# Stepper_Motor6.net
KiCad netlist of a schematic drawn in Altium Designer
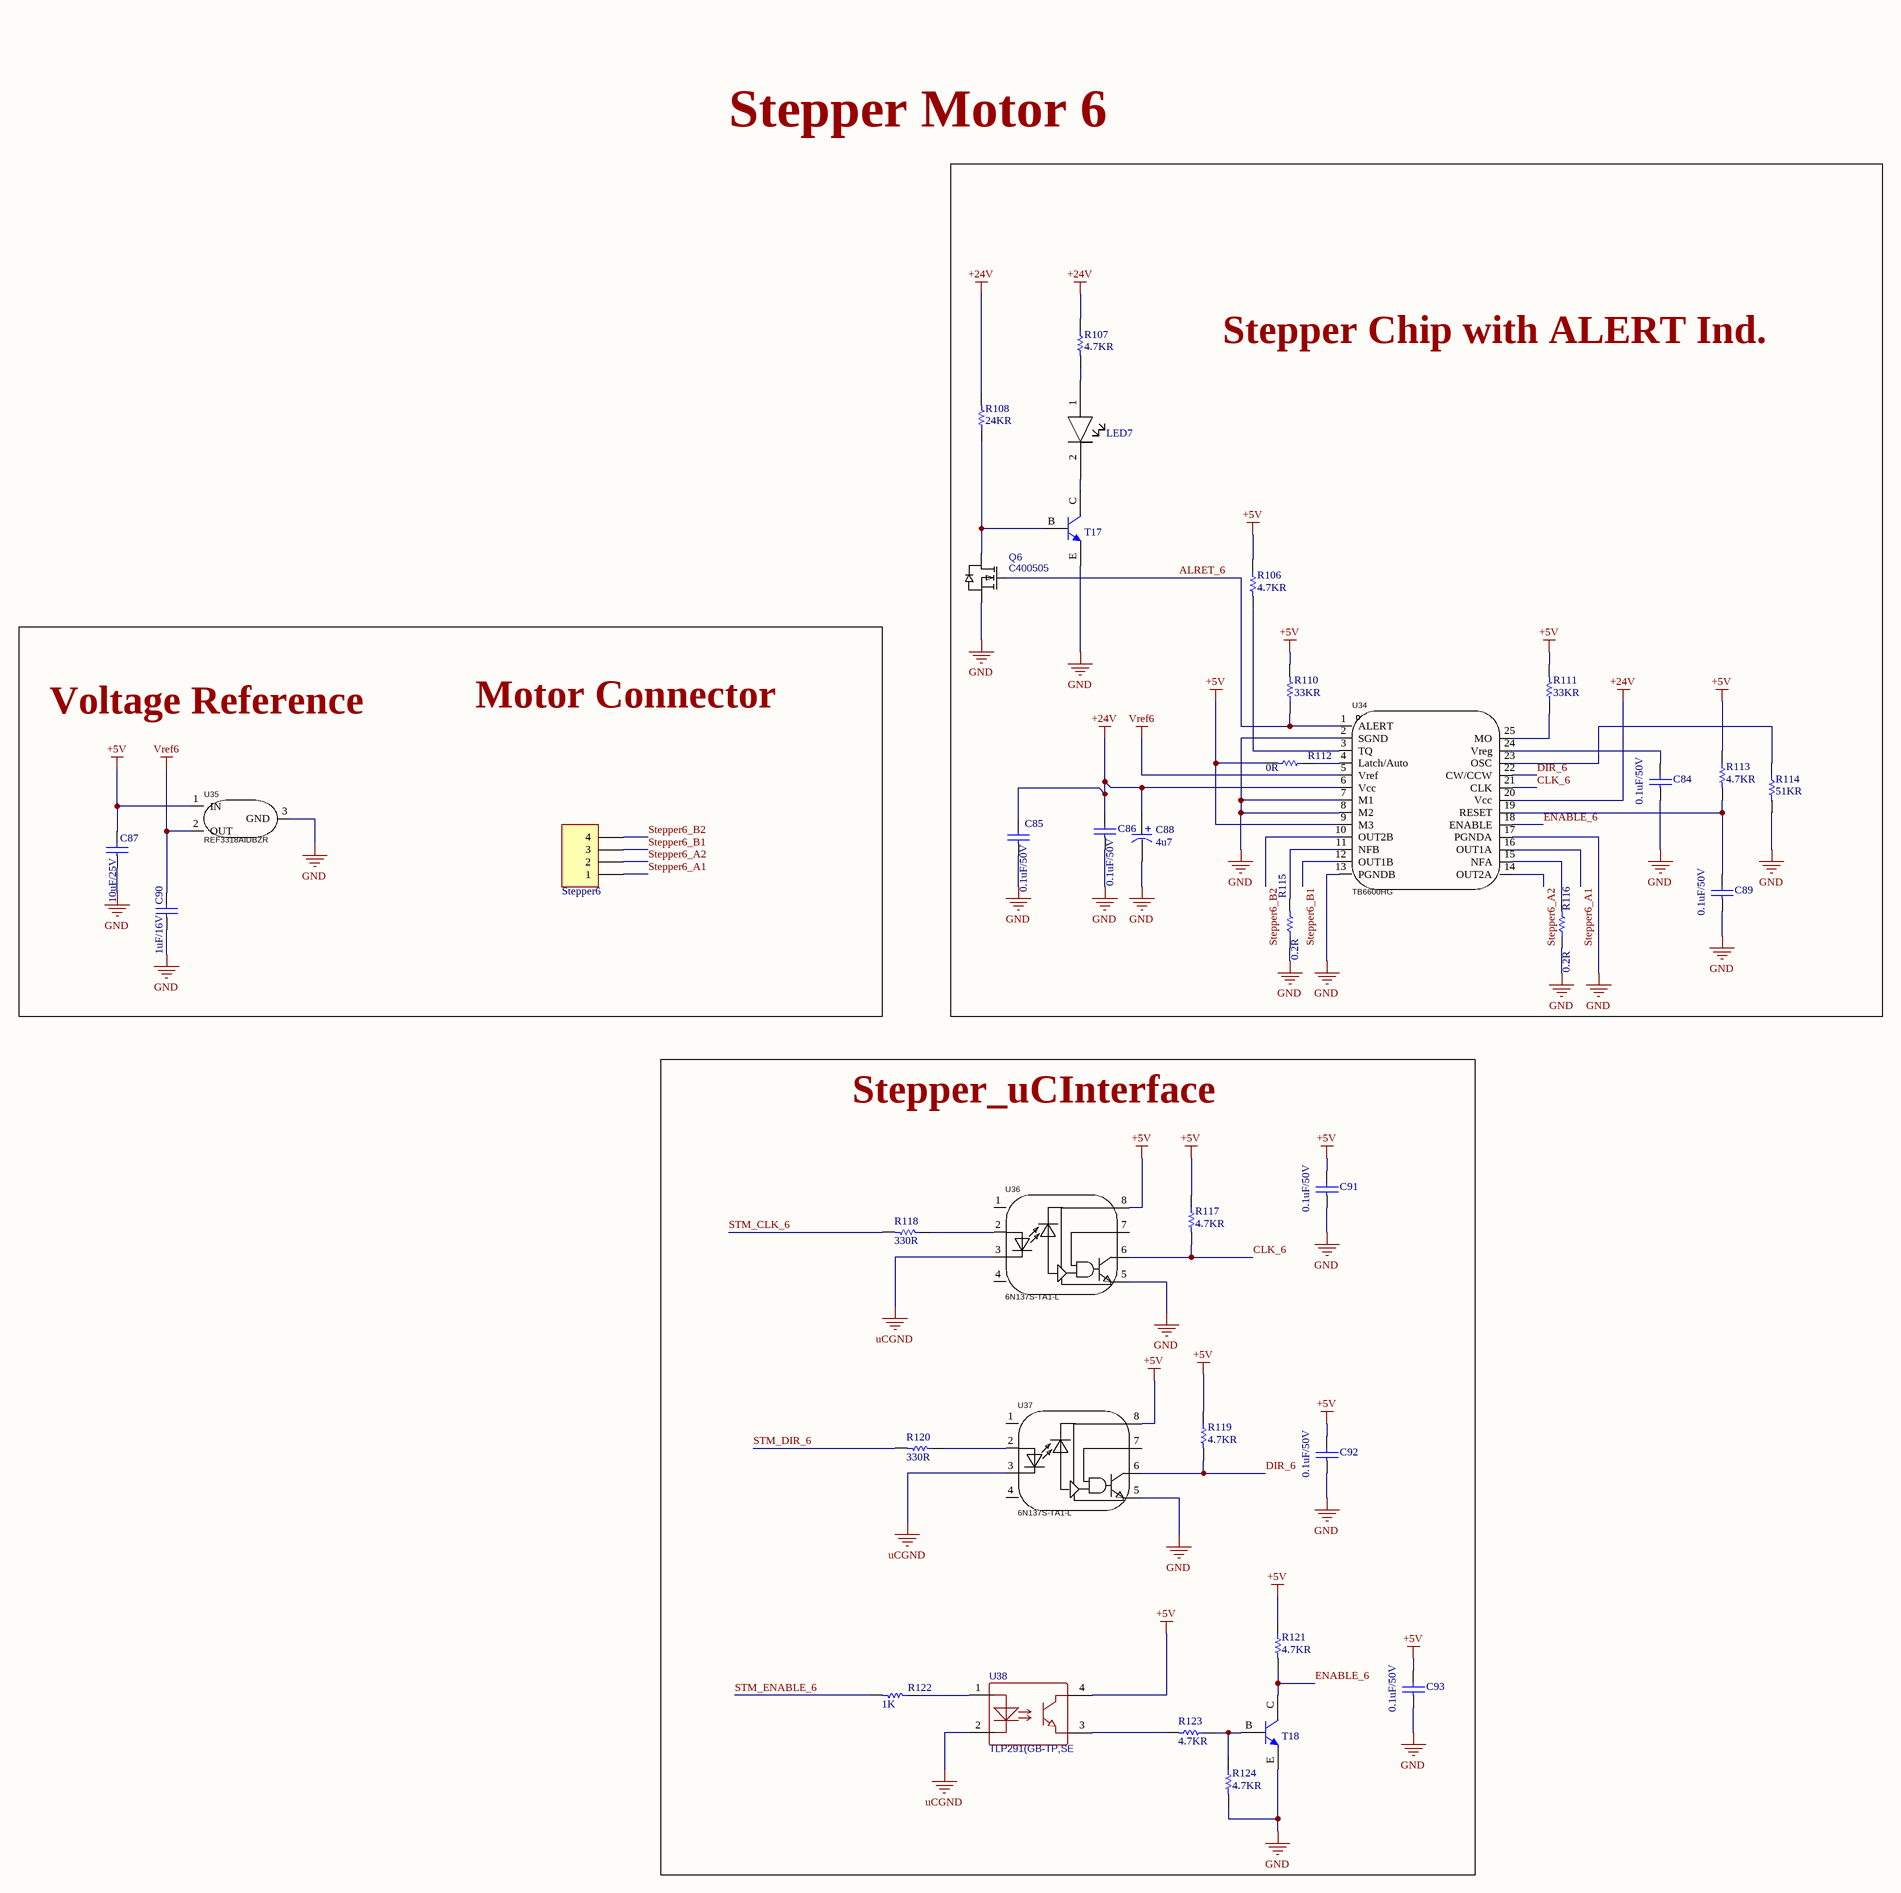
[diagram p0: Stepper Motor6.SchDoc]

(export (version "E")
  (design (tool "Eeschema 10.0.6"))
  (components
    (comp (ref "C84")
      (value "0.1uF/50V")
      (footprint "PCBComponent_1")
      (description "C1591")
      (fields (field (name "CREATED BY") "NourAldin"))
      (libsource (lib "0603 Capacitor") (part "0603 Capacitor"))
    )
    (comp (ref "C85")
      (value "0.1uF/50V")
      (footprint "PCBComponent_1")
      (description "C1591")
      (fields (field (name "CREATED BY") "NourAldin"))
      (libsource (lib "0603 Capacitor") (part "0603 Capacitor"))
    )
    (comp (ref "C86")
      (value "0.1uF/50V")
      (footprint "PCBComponent_1")
      (description "C1591")
      (fields (field (name "CREATED BY") "NourAldin"))
      (libsource (lib "0603 Capacitor") (part "0603 Capacitor"))
    )
    (comp (ref "C87")
      (value "10uF/25V")
      (footprint "PCBComponent_1")
      (description "C96446")
      (fields (field (name "CREATED BY") "NourAldin"))
      (libsource (lib "0603 Capacitor") (part "0603 Capacitor"))
    )
    (comp (ref "C88")
      (value "4u7")
      (footprint "CAPLEAD_D6.3mm")
      (description "C2691843")
      (fields
        (field (name "MANUFACTURER") "KEMET")
        (field (name "MANUFACTURER PART NUMBER") "A759EQ475M2AAAE160")
      )
      (libsource (lib "GlobalLib") (part "A759EQ475M2AAAE160"))
    )
    (comp (ref "C89")
      (value "0.1uF/50V")
      (footprint "PCBComponent_1")
      (description "C1591")
      (fields (field (name "CREATED BY") "NourAldin"))
      (libsource (lib "0603 Capacitor") (part "0603 Capacitor"))
    )
    (comp (ref "C90")
      (value "1uF/16V")
      (footprint "PCBComponent_1")
      (description "C1592")
      (fields (field (name "CREATED BY") "NourAldin"))
      (libsource (lib "0603 Capacitor") (part "0603 Capacitor"))
    )
    (comp (ref "C91")
      (value "0.1uF/50V")
      (footprint "PCBComponent_1")
      (description "C1591")
      (fields (field (name "CREATED BY") "NourAldin"))
      (libsource (lib "0603 Capacitor") (part "0603 Capacitor"))
    )
    (comp (ref "C92")
      (value "0.1uF/50V")
      (footprint "PCBComponent_1")
      (description "C1591")
      (fields (field (name "CREATED BY") "NourAldin"))
      (libsource (lib "0603 Capacitor") (part "0603 Capacitor"))
    )
    (comp (ref "C93")
      (value "0.1uF/50V")
      (footprint "PCBComponent_1")
      (description "C1591")
      (fields (field (name "CREATED BY") "NourAldin"))
      (libsource (lib "0603 Capacitor") (part "0603 Capacitor"))
    )
    (comp (ref "LED7")
      (value "1206 LED")
      (footprint "1206 LED")
      (description "C434438")
      (fields (field (name "CREATED BY") "NourAldin"))
      (libsource (lib "1206 LED") (part "1206 LED"))
    )
    (comp (ref "Q6")
      (value "C400505")
      (footprint "SOT-23-3_L2.9-W1.3-P1.90-LS2.4-BR")
      (fields
        (field (name "MANUFACTURER") "YANGJIE(扬杰)")
        (field (name "MANUFACTURER PART") "BSS138")
        (field (name "CONTRIBUTOR") "LCSC")
      )
      (libsource (lib "DIVERSE") (part "BSS138_MOSFET"))
    )
    (comp (ref "R106")
      (value "4.7KR")
      (footprint "R0402")
      (description "C105871")
      (libsource (lib "DIVERSE") (part "0402 Resistor"))
    )
    (comp (ref "R107")
      (value "4.7KR")
      (footprint "R0402")
      (description "C105871")
      (libsource (lib "DIVERSE") (part "0402 Resistor"))
    )
    (comp (ref "R108")
      (value "24KR")
      (footprint "RESC1608X06N")
      (description "C2930081")
      (fields (field (name "CREATED BY") "NourAldin"))
      (libsource (lib "0603 Resistor") (part "0603 Resistor"))
    )
    (comp (ref "R110")
      (value "33KR")
      (footprint "RESC1608X06N")
      (description "C126359")
      (fields (field (name "CREATED BY") "NourAldin"))
      (libsource (lib "0603 Resistor") (part "0603 Resistor"))
    )
    (comp (ref "R111")
      (value "33KR")
      (footprint "RESC1608X06N")
      (description "C126359")
      (fields (field (name "CREATED BY") "NourAldin"))
      (libsource (lib "0603 Resistor") (part "0603 Resistor"))
    )
    (comp (ref "R112")
      (value "0R")
      (footprint "RESC1608X06N")
      (description "C100044")
      (fields (field (name "CREATED BY") "NourAldin"))
      (libsource (lib "0603 Resistor") (part "0603 Resistor"))
    )
    (comp (ref "R113")
      (value "4.7KR")
      (footprint "R0402")
      (description "C105871")
      (libsource (lib "DIVERSE") (part "0402 Resistor"))
    )
    (comp (ref "R114")
      (value "51KR")
      (footprint "R0402")
      (description "C107230")
      (libsource (lib "DIVERSE") (part "0402 Resistor"))
    )
    (comp (ref "R115")
      (value "0.2R")
      (footprint "RESC6431X12N")
      (description "C2903473")
      (fields (field (name "CREATED BY") "NourAldin"))
      (libsource (lib "2512 Resistor") (part "2512 Resistor"))
    )
    (comp (ref "R116")
      (value "0.2R")
      (footprint "RESC6431X12N")
      (description "C2903473")
      (fields (field (name "CREATED BY") "NourAldin"))
      (libsource (lib "2512 Resistor") (part "2512 Resistor"))
    )
    (comp (ref "R117")
      (value "4.7KR")
      (footprint "R0402")
      (description "C105871")
      (libsource (lib "DIVERSE") (part "0402 Resistor"))
    )
    (comp (ref "R118")
      (value "330R")
      (footprint "R0402")
      (description "C105875")
      (libsource (lib "DIVERSE") (part "0402 Resistor"))
    )
    (comp (ref "R119")
      (value "4.7KR")
      (footprint "R0402")
      (description "C105871")
      (libsource (lib "DIVERSE") (part "0402 Resistor"))
    )
    (comp (ref "R120")
      (value "330R")
      (footprint "R0402")
      (description "C105875")
      (libsource (lib "DIVERSE") (part "0402 Resistor"))
    )
    (comp (ref "R121")
      (value "4.7KR")
      (footprint "R0402")
      (description "C105871")
      (libsource (lib "DIVERSE") (part "0402 Resistor"))
    )
    (comp (ref "R122")
      (value "1K")
      (footprint "R0402")
      (description "C106235")
      (libsource (lib "DIVERSE") (part "0402 Resistor"))
    )
    (comp (ref "R123")
      (value "4.7KR")
      (footprint "R0402")
      (description "C105871")
      (libsource (lib "DIVERSE") (part "0402 Resistor"))
    )
    (comp (ref "R124")
      (value "4.7KR")
      (footprint "R0402")
      (description "C105871")
      (libsource (lib "DIVERSE") (part "0402 Resistor"))
    )
    (comp (ref "Stepper6")
      (value "Header 4 Pin Polar")
      (footprint "PCBComponent_1")
      (description "C144395")
      (libsource (lib "Header 4 Pin Polar") (part "Header 4 Pin Polar"))
    )
    (comp (ref "T17")
      (value "MMBT3904 Transistor")
      (footprint "MMBT3904")
      (description "C108429")
      (fields (field (name "CREATED BY") "NourAldin"))
      (libsource (lib "MMBT3904 Transistor") (part "MMBT3904 Transistor"))
    )
    (comp (ref "T18")
      (value "MMBT3904 Transistor")
      (footprint "MMBT3904")
      (description "C108429")
      (fields (field (name "CREATED BY") "NourAldin"))
      (libsource (lib "MMBT3904 Transistor") (part "MMBT3904 Transistor"))
    )
    (comp (ref "U34")
      (value "TB6600HG")
      (footprint "HZIP25-P-1.0_TB6600HG - HEATSINK")
      (description "C66042")
      (fields (field (name "MANUFACTURER") "TOSHIBA(东芝)"))
      (libsource (lib "LIB") (part "TB6600HG"))
    )
    (comp (ref "U35")
      (value "REF3318AIDBZR")
      (footprint "SOT-23-3_L2.9-W1.3-P1.90-LS2.4-BR")
      (description "C115877")
      (fields (field (name "MANUFACTURER") "TI(德州仪器)") (field (name "TOLERANCE") "±0.15%"))
      (libsource (lib "LIB") (part "REF3318AIDBZR"))
    )
    (comp (ref "U36")
      (value "6N137S-TA1-L")
      (footprint "SOP-8_L9.8-W6.6-P2.54-LS10.3-BL")
      (description "C92651")
      (fields (field (name "MANUFACTURER") "LITEON(光宝)"))
      (libsource (lib "LIB") (part "6N137S-TA1-L"))
    )
    (comp (ref "U37")
      (value "6N137S-TA1-L")
      (footprint "SOP-8_L9.8-W6.6-P2.54-LS10.3-BL")
      (description "C92651")
      (fields (field (name "MANUFACTURER") "LITEON(光宝)"))
      (libsource (lib "LIB") (part "6N137S-TA1-L"))
    )
    (comp (ref "U38")
      (value "TLP291(GB-TP,SE")
      (footprint "SOP-4-1.27mm")
      (description "C55144")
      (libsource (lib "CO2_Lib") (part "TLP291(GB-TP,SE(T"))
    )
  )
  (nets
    (net (code "1") (name "+5V") (class "Default")
      (node (ref "C87") (pin "2") (pinfunction "2_2") (pintype "passive"))
      (node (ref "C91") (pin "2") (pinfunction "2_2") (pintype "passive"))
      (node (ref "C92") (pin "2") (pinfunction "2_2") (pintype "passive"))
      (node (ref "C93") (pin "2") (pinfunction "2_2") (pintype "passive"))
      (node (ref "R106") (pin "1") (pinfunction "1_1") (pintype "passive"))
      (node (ref "R110") (pin "2") (pinfunction "2_2") (pintype "passive"))
      (node (ref "R111") (pin "2") (pinfunction "2_2") (pintype "passive"))
      (node (ref "R112") (pin "2") (pinfunction "2_2") (pintype "passive"))
      (node (ref "R113") (pin "1") (pinfunction "1_1") (pintype "passive"))
      (node (ref "R117") (pin "1") (pinfunction "1_1") (pintype "passive"))
      (node (ref "R119") (pin "1") (pinfunction "1_1") (pintype "passive"))
      (node (ref "R121") (pin "1") (pinfunction "1_1") (pintype "passive"))
      (node (ref "U34") (pin "9") (pinfunction "M3_9") (pintype "passive"))
      (node (ref "U35") (pin "1") (pinfunction "IN_1") (pintype "passive"))
      (node (ref "U36") (pin "8") (pinfunction "8_8") (pintype "passive"))
      (node (ref "U37") (pin "8") (pinfunction "8_8") (pintype "passive"))
      (node (ref "U38") (pin "4") (pinfunction "4_4") (pintype "passive"))
    )
    (net (code "2") (name "+24V") (class "Default")
      (node (ref "C85") (pin "2") (pinfunction "2_2") (pintype "passive"))
      (node (ref "C86") (pin "2") (pinfunction "2_2") (pintype "passive"))
      (node (ref "C88") (pin "1") (pinfunction "1_1") (pintype "passive"))
      (node (ref "R107") (pin "1") (pinfunction "1_1") (pintype "passive"))
      (node (ref "R108") (pin "2") (pinfunction "2_2") (pintype "passive"))
      (node (ref "U34") (pin "20") (pinfunction "Vcc_20") (pintype "passive"))
      (node (ref "U34") (pin "6") (pinfunction "Vcc_6") (pintype "passive"))
    )
    (net (code "3") (name "/ALRET_6") (class "Default")
      (node (ref "Q6") (pin "1") (pinfunction "G_1") (pintype "passive"))
      (node (ref "R110") (pin "1") (pinfunction "1_1") (pintype "passive"))
      (node (ref "U34") (pin "1") (pinfunction "ALERT_1") (pintype "passive"))
    )
    (net (code "4") (name "/CLK_6") (class "Default")
      (node (ref "R117") (pin "2") (pinfunction "2_2") (pintype "passive"))
      (node (ref "U34") (pin "21") (pinfunction "CLK_21") (pintype "passive"))
      (node (ref "U36") (pin "6") (pinfunction "6_6") (pintype "passive"))
    )
    (net (code "5") (name "/DIR_6") (class "Default")
      (node (ref "R119") (pin "2") (pinfunction "2_2") (pintype "passive"))
      (node (ref "U34") (pin "22") (pinfunction "CW/CCW_22") (pintype "passive"))
      (node (ref "U37") (pin "6") (pinfunction "6_6") (pintype "passive"))
    )
    (net (code "6") (name "/ENABLE_6") (class "Default")
      (node (ref "R121") (pin "2") (pinfunction "2_2") (pintype "passive"))
      (node (ref "T18") (pin "C") (pinfunction "C_C") (pintype "passive"))
      (node (ref "U34") (pin "18") (pinfunction "ENABLE_18") (pintype "passive"))
    )
    (net (code "7") (name "/STM_CLK_6") (class "Default")
      (node (ref "R118") (pin "2") (pinfunction "2_2") (pintype "passive"))
    )
    (net (code "8") (name "/STM_DIR_6") (class "Default")
      (node (ref "R120") (pin "2") (pinfunction "2_2") (pintype "passive"))
    )
    (net (code "9") (name "/STM_ENABLE_6") (class "Default")
      (node (ref "R122") (pin "2") (pinfunction "2_2") (pintype "passive"))
    )
    (net (code "10") (name "/Stepper6_A1") (class "Default")
      (node (ref "Stepper6") (pin "1") (pinfunction "1_1") (pintype "passive"))
      (node (ref "U34") (pin "16") (pinfunction "OUT1A_16") (pintype "passive"))
    )
    (net (code "11") (name "/Stepper6_A2") (class "Default")
      (node (ref "Stepper6") (pin "2") (pinfunction "2_2") (pintype "passive"))
      (node (ref "U34") (pin "14") (pinfunction "OUT2A_14") (pintype "passive"))
    )
    (net (code "12") (name "/Stepper6_B1") (class "Default")
      (node (ref "Stepper6") (pin "3") (pinfunction "3_3") (pintype "passive"))
      (node (ref "U34") (pin "12") (pinfunction "OUT1B_12") (pintype "passive"))
    )
    (net (code "13") (name "/Stepper6_B2") (class "Default")
      (node (ref "Stepper6") (pin "4") (pinfunction "4_4") (pintype "passive"))
      (node (ref "U34") (pin "10") (pinfunction "OUT2B_10") (pintype "passive"))
    )
    (net (code "14") (name "GND") (class "Default")
      (node (ref "C84") (pin "1") (pinfunction "1_1") (pintype "passive"))
      (node (ref "C85") (pin "1") (pinfunction "1_1") (pintype "passive"))
      (node (ref "C86") (pin "1") (pinfunction "1_1") (pintype "passive"))
      (node (ref "C87") (pin "1") (pinfunction "1_1") (pintype "passive"))
      (node (ref "C88") (pin "2") (pinfunction "2_2") (pintype "passive"))
      (node (ref "C89") (pin "1") (pinfunction "1_1") (pintype "passive"))
      (node (ref "C90") (pin "1") (pinfunction "1_1") (pintype "passive"))
      (node (ref "C91") (pin "1") (pinfunction "1_1") (pintype "passive"))
      (node (ref "C92") (pin "1") (pinfunction "1_1") (pintype "passive"))
      (node (ref "C93") (pin "1") (pinfunction "1_1") (pintype "passive"))
      (node (ref "Q6") (pin "2") (pinfunction "S_2") (pintype "passive"))
      (node (ref "R114") (pin "2") (pinfunction "2_2") (pintype "passive"))
      (node (ref "R115") (pin "1") (pinfunction "1_1") (pintype "passive"))
      (node (ref "R116") (pin "1") (pinfunction "1_1") (pintype "passive"))
      (node (ref "R124") (pin "2") (pinfunction "2_2") (pintype "passive"))
      (node (ref "T17") (pin "E") (pinfunction "E_E") (pintype "passive"))
      (node (ref "T18") (pin "E") (pinfunction "E_E") (pintype "passive"))
      (node (ref "U34") (pin "13") (pinfunction "PGNDB_13") (pintype "passive"))
      (node (ref "U34") (pin "17") (pinfunction "PGNDA_17") (pintype "passive"))
      (node (ref "U34") (pin "2") (pinfunction "SGND_2") (pintype "passive"))
      (node (ref "U34") (pin "7") (pinfunction "M1_7") (pintype "passive"))
      (node (ref "U34") (pin "8") (pinfunction "M2_8") (pintype "passive"))
      (node (ref "U35") (pin "3") (pinfunction "GND_3") (pintype "passive"))
      (node (ref "U36") (pin "5") (pinfunction "5_5") (pintype "passive"))
      (node (ref "U37") (pin "5") (pinfunction "5_5") (pintype "passive"))
    )
    (net (code "15") (name "Net-(LED7-Pad1)") (class "Default")
      (node (ref "LED7") (pin "1") (pinfunction "1_1") (pintype "passive"))
      (node (ref "R107") (pin "2") (pinfunction "2_2") (pintype "passive"))
    )
    (net (code "16") (name "Net-(LED7-Pad2)") (class "Default")
      (node (ref "LED7") (pin "2") (pinfunction "2_2") (pintype "passive"))
      (node (ref "T17") (pin "C") (pinfunction "C_C") (pintype "passive"))
    )
    (net (code "17") (name "Net-(Q6-D)") (class "Default")
      (node (ref "Q6") (pin "3") (pinfunction "D_3") (pintype "passive"))
      (node (ref "R108") (pin "1") (pinfunction "1_1") (pintype "passive"))
      (node (ref "T17") (pin "B") (pinfunction "B_B") (pintype "passive"))
    )
    (net (code "18") (name "Net-(R118-Pad1)") (class "Default")
      (node (ref "R118") (pin "1") (pinfunction "1_1") (pintype "passive"))
      (node (ref "U36") (pin "2") (pinfunction "2_2") (pintype "passive"))
    )
    (net (code "19") (name "Net-(R120-Pad1)") (class "Default")
      (node (ref "R120") (pin "1") (pinfunction "1_1") (pintype "passive"))
      (node (ref "U37") (pin "2") (pinfunction "2_2") (pintype "passive"))
    )
    (net (code "20") (name "Net-(R122-Pad1)") (class "Default")
      (node (ref "R122") (pin "1") (pinfunction "1_1") (pintype "passive"))
      (node (ref "U38") (pin "1") (pinfunction "1_1") (pintype "passive"))
    )
    (net (code "21") (name "Net-(R123-Pad1)") (class "Default")
      (node (ref "R123") (pin "1") (pinfunction "1_1") (pintype "passive"))
      (node (ref "R124") (pin "1") (pinfunction "1_1") (pintype "passive"))
      (node (ref "T18") (pin "B") (pinfunction "B_B") (pintype "passive"))
    )
    (net (code "22") (name "Net-(R123-Pad2)") (class "Default")
      (node (ref "R123") (pin "2") (pinfunction "2_2") (pintype "passive"))
      (node (ref "U38") (pin "3") (pinfunction "3_3") (pintype "passive"))
    )
    (net (code "23") (name "Net-(U34-Latch{slash}Auto)") (class "Default")
      (node (ref "R112") (pin "1") (pinfunction "1_1") (pintype "passive"))
      (node (ref "U34") (pin "4") (pinfunction "Latch/Auto_4") (pintype "passive"))
    )
    (net (code "24") (name "Net-(U34-MO)") (class "Default")
      (node (ref "R111") (pin "1") (pinfunction "1_1") (pintype "passive"))
      (node (ref "U34") (pin "25") (pinfunction "MO_25") (pintype "passive"))
    )
    (net (code "25") (name "Net-(U34-NFA)") (class "Default")
      (node (ref "R116") (pin "2") (pinfunction "2_2") (pintype "passive"))
      (node (ref "U34") (pin "15") (pinfunction "NFA_15") (pintype "passive"))
    )
    (net (code "26") (name "Net-(U34-NFB)") (class "Default")
      (node (ref "R115") (pin "2") (pinfunction "2_2") (pintype "passive"))
      (node (ref "U34") (pin "11") (pinfunction "NFB_11") (pintype "passive"))
    )
    (net (code "27") (name "Net-(U34-OSC)") (class "Default")
      (node (ref "R114") (pin "1") (pinfunction "1_1") (pintype "passive"))
      (node (ref "U34") (pin "23") (pinfunction "OSC_23") (pintype "passive"))
    )
    (net (code "28") (name "Net-(U34-RESET)") (class "Default")
      (node (ref "C89") (pin "2") (pinfunction "2_2") (pintype "passive"))
      (node (ref "R113") (pin "2") (pinfunction "2_2") (pintype "passive"))
      (node (ref "U34") (pin "19") (pinfunction "RESET_19") (pintype "passive"))
    )
    (net (code "29") (name "Net-(U34-TQ)") (class "Default")
      (node (ref "R106") (pin "2") (pinfunction "2_2") (pintype "passive"))
      (node (ref "U34") (pin "3") (pinfunction "TQ_3") (pintype "passive"))
    )
    (net (code "30") (name "Net-(U34-Vreg)") (class "Default")
      (node (ref "C84") (pin "2") (pinfunction "2_2") (pintype "passive"))
      (node (ref "U34") (pin "24") (pinfunction "Vreg_24") (pintype "passive"))
    )
    (net (code "31") (name "Vref6") (class "Default")
      (node (ref "C90") (pin "2") (pinfunction "2_2") (pintype "passive"))
      (node (ref "U34") (pin "5") (pinfunction "Vref_5") (pintype "passive"))
      (node (ref "U35") (pin "2") (pinfunction "OUT_2") (pintype "passive"))
    )
    (net (code "32") (name "uCGND") (class "Default")
      (node (ref "U36") (pin "3") (pinfunction "3_3") (pintype "passive"))
      (node (ref "U37") (pin "3") (pinfunction "3_3") (pintype "passive"))
      (node (ref "U38") (pin "2") (pinfunction "2_2") (pintype "passive"))
    )
    (net (code "33") (name "unconnected-(U36-NC-Pad1)") (class "Default")
      (node (ref "U36") (pin "1") (pinfunction "NC_1") (pintype "passive"))
    )
    (net (code "34") (name "unconnected-(U36-NC-Pad4)") (class "Default")
      (node (ref "U36") (pin "4") (pinfunction "NC_4") (pintype "passive"))
    )
    (net (code "35") (name "unconnected-(U36-Pad7)") (class "Default")
      (node (ref "U36") (pin "7") (pinfunction "7_7") (pintype "passive"))
    )
    (net (code "36") (name "unconnected-(U37-NC-Pad1)") (class "Default")
      (node (ref "U37") (pin "1") (pinfunction "NC_1") (pintype "passive"))
    )
    (net (code "37") (name "unconnected-(U37-NC-Pad4)") (class "Default")
      (node (ref "U37") (pin "4") (pinfunction "NC_4") (pintype "passive"))
    )
    (net (code "38") (name "unconnected-(U37-Pad7)") (class "Default")
      (node (ref "U37") (pin "7") (pinfunction "7_7") (pintype "passive"))
    )
  )
)
